# CCU_Sheet.net
KiCad netlist of a schematic drawn in Altium Designer
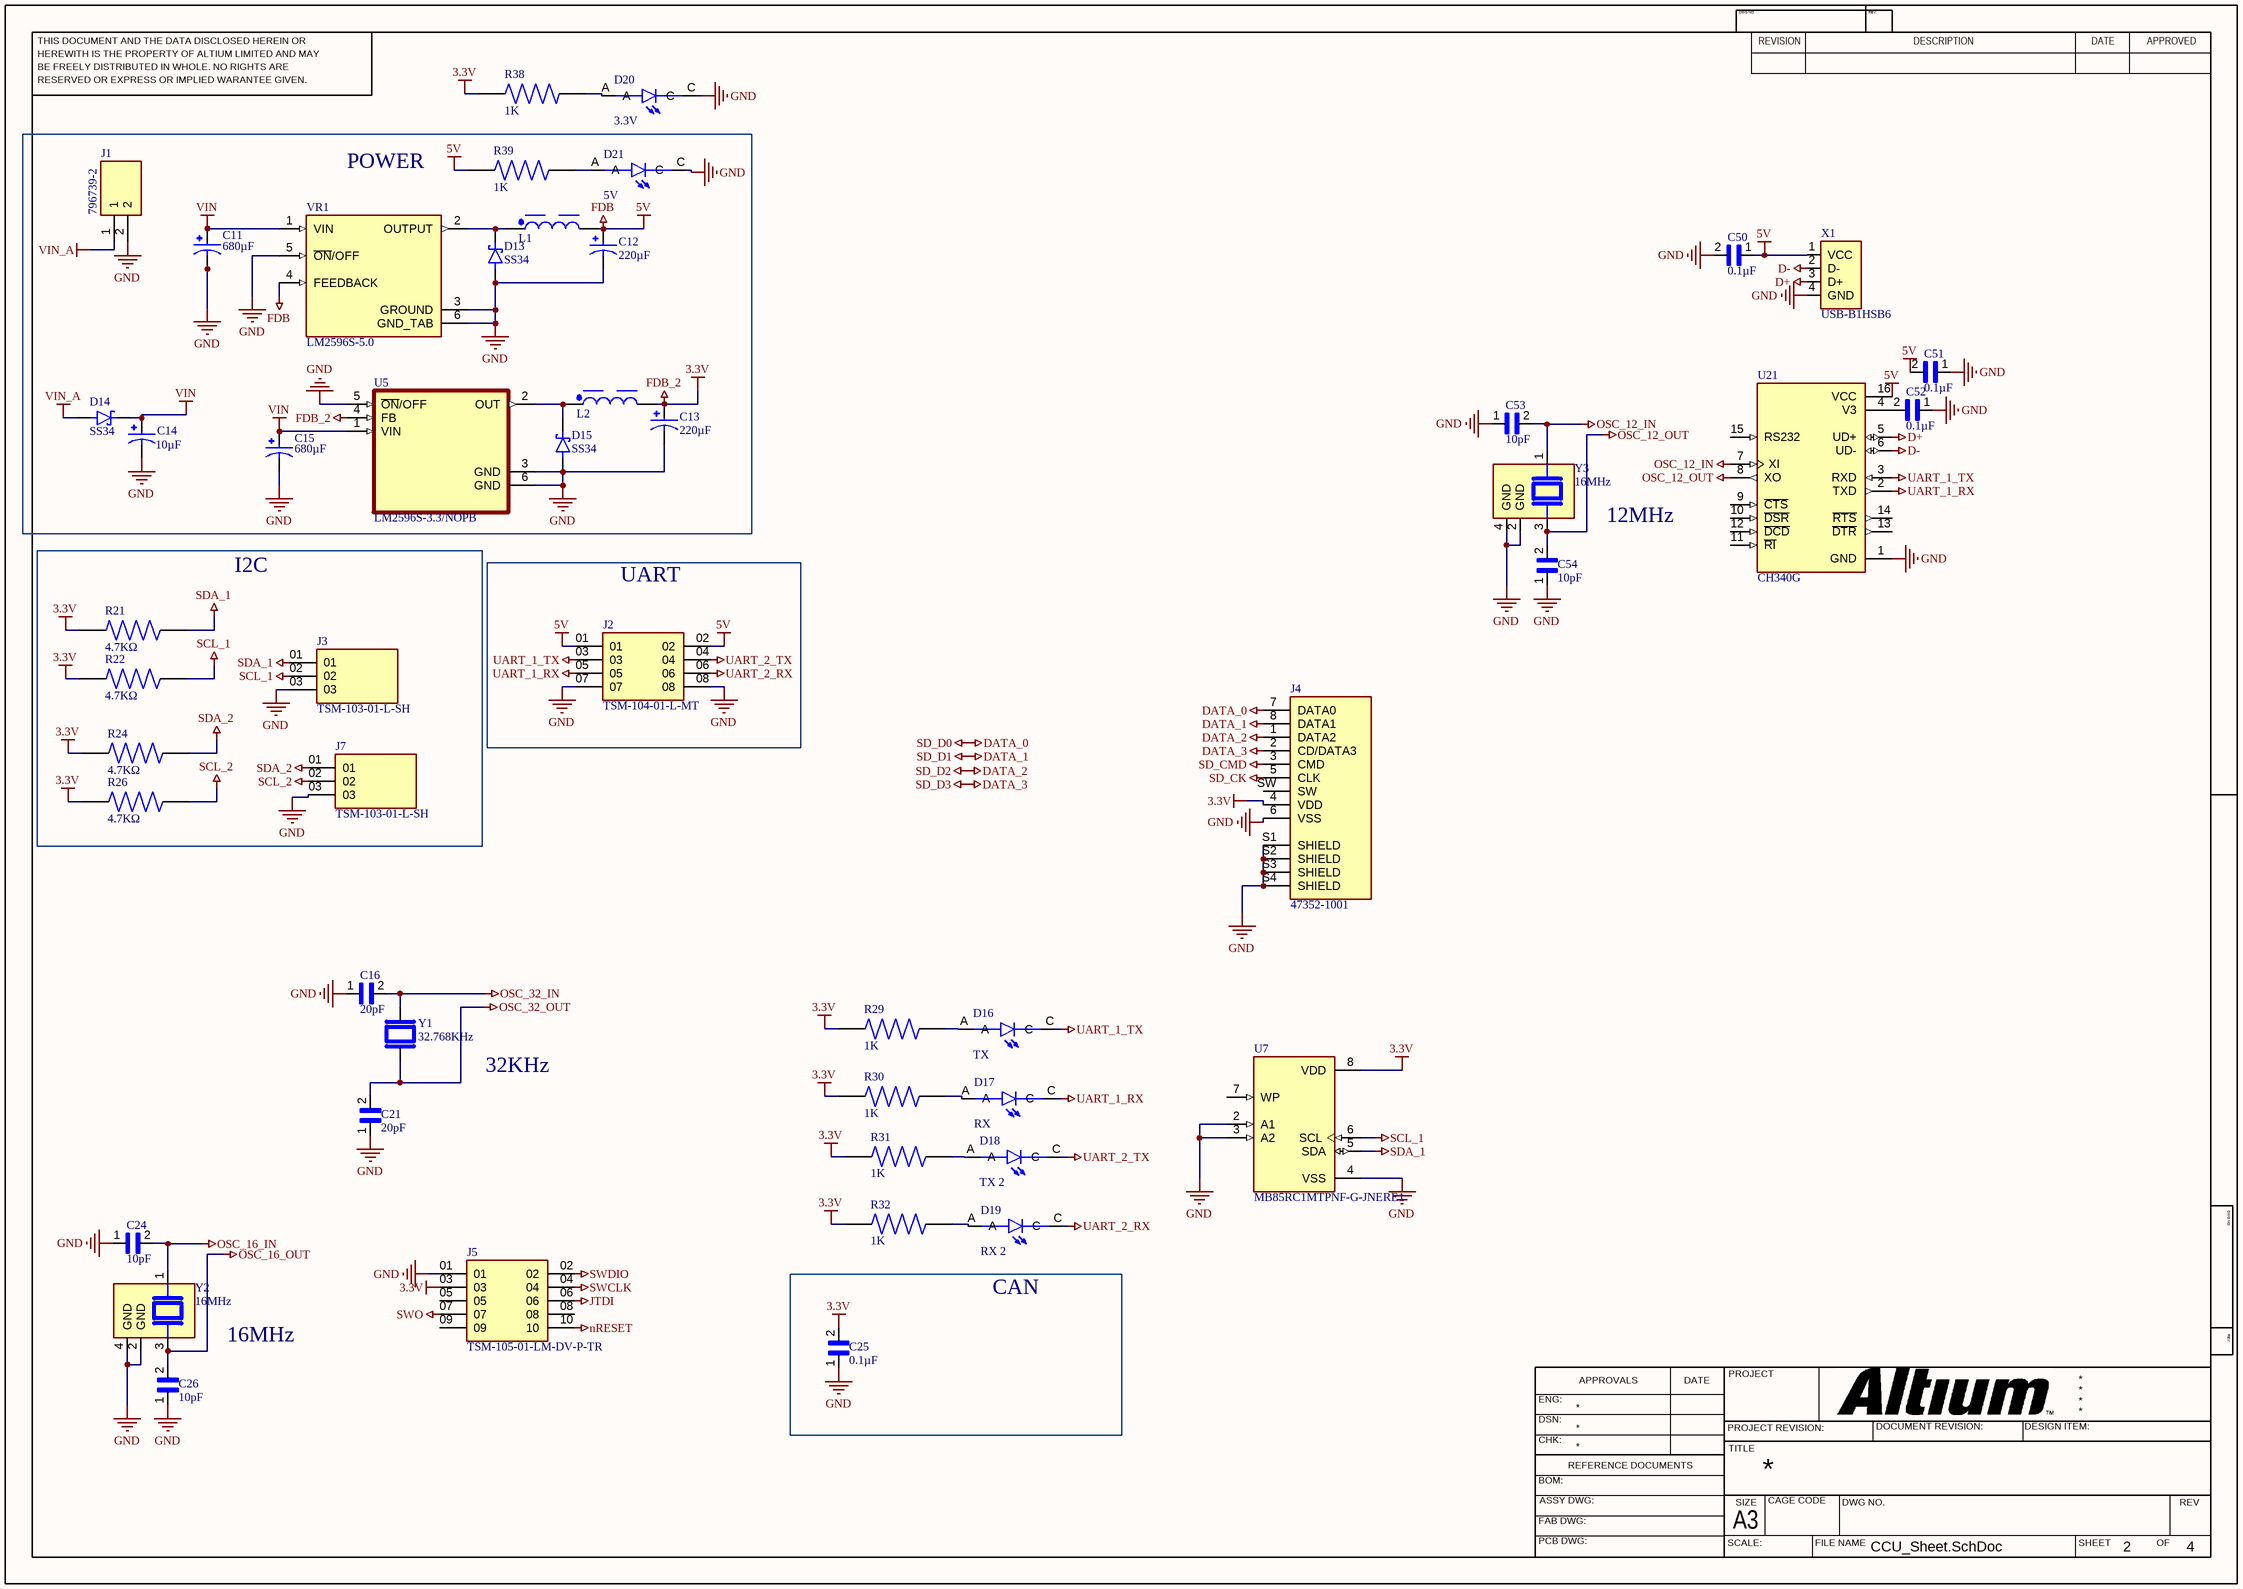
[diagram p0: CCU_Sheet.SchDoc]

(export (version "E")
  (design (tool "Eeschema 10.0.6"))
  (components
    (comp (ref "C11")
      (value "680µF")
      (footprint "CAP_EEEFN1E681UV")
      (description "CAP ALUM 680UF 20% 25V SMD")
      (fields (field (name "MF") "Panasonic Electronic Components") (field (name "MP") "EEE-FN1E681UV"))
      (libsource (lib "EEEFN1E681UV") (part "EEEFN1E681UV"))
    )
    (comp (ref "C12")
      (value "220µF")
      (footprint "CAP_EEEFP1V221AV")
      (description "CAP ALUM 220UF 20% 35V SMD")
      (fields (field (name "MF") "Panasonic Electronic Components") (field (name "MP") "EEE-FP1V221AV"))
      (libsource (lib "") (part "EEEFP1V221AV_1"))
    )
    (comp (ref "C13")
      (value "220µF")
      (footprint "CAP_EEEFP1V221AV")
      (description "CAP ALUM 220UF 20% 35V SMD")
      (fields (field (name "MF") "Panasonic Electronic Components") (field (name "MP") "EEE-FP1V221AV"))
      (libsource (lib "EEEFP1V221AV") (part "EEEFP1V221AV"))
    )
    (comp (ref "C14")
      (value "10µF")
      (footprint "CAPPRD500W50D500H1100")
      (description "10ÂµF 25V Aluminum Electrolytic Capacitors Radial, Can 2000 Hrs @ 85Â°C")
      (fields (field (name "MF") "Panasonic") (field (name "MP") "ECEA1EN100UB"))
      (libsource (lib "ECEA1EN100UB") (part "ECEA1EN100UB"))
    )
    (comp (ref "C15")
      (value "680µF")
      (footprint "CAP_EEEFN1E681UV")
      (description "CAP ALUM 680UF 20% 25V SMD")
      (fields (field (name "MF") "Panasonic Electronic Components") (field (name "MP") "EEE-FN1E681UV"))
      (libsource (lib "") (part "EEEFN1E681UV_1"))
    )
    (comp (ref "C16")
      (value "20pF")
      (footprint "CAPC1005X61N")
      (fields (field (name "MP") "VJ0402D200FXAAJ"))
      (libsource (lib "VJ0402D200FXAAJ") (part "VJ0402D200FXAAJ"))
    )
    (comp (ref "C21")
      (value "20pF")
      (footprint "CAPC1005X61N")
      (fields (field (name "MP") "VJ0402D200FXAAJ"))
      (libsource (lib "") (part "VJ0402D200FXAAJ_1"))
    )
    (comp (ref "C24")
      (value "10pF")
      (footprint "CAPC1005X61N")
      (fields (field (name "MP") "VJ0402D200FXAAJ"))
      (libsource (lib "VJ0402D200FXAAJ") (part "VJ0402D200FXAAJ"))
    )
    (comp (ref "C25")
      (value "0.1µF")
      (footprint "CAPC1608X90N")
      (description "Multilayer Ceramic Capacitors MLCC - SMD/SMT")
      (fields (field (name "MP") "06035C104MAZ2A"))
      (libsource (lib "") (part "06035C104MAZ2A_1"))
    )
    (comp (ref "C26")
      (value "10pF")
      (footprint "CAPC1005X61N")
      (fields (field (name "MP") "VJ0402D200FXAAJ"))
      (libsource (lib "") (part "VJ0402D200FXAAJ_1"))
    )
    (comp (ref "C50")
      (value "0.1µF")
      (footprint "CAPC1608X90N")
      (description "Multilayer Ceramic Capacitors MLCC - SMD/SMT")
      (fields (field (name "MP") "06035C104MAZ2A"))
      (libsource (lib "06035C104MAZ2A") (part "06035C104MAZ2A"))
    )
    (comp (ref "C51")
      (value "0.1µF")
      (footprint "CAPC1608X90N")
      (description "Multilayer Ceramic Capacitors MLCC - SMD/SMT")
      (fields (field (name "MP") "06035C104MAZ2A"))
      (libsource (lib "06035C104MAZ2A") (part "06035C104MAZ2A"))
    )
    (comp (ref "C52")
      (value "0.1µF")
      (footprint "CAPC1608X90N")
      (description "Multilayer Ceramic Capacitors MLCC - SMD/SMT")
      (fields (field (name "MP") "06035C104MAZ2A"))
      (libsource (lib "06035C104MAZ2A") (part "06035C104MAZ2A"))
    )
    (comp (ref "C53")
      (value "10pF")
      (footprint "CAPC1005X61N")
      (fields (field (name "MP") "VJ0402D200FXAAJ"))
      (libsource (lib "VJ0402D200FXAAJ") (part "VJ0402D200FXAAJ"))
    )
    (comp (ref "C54")
      (value "10pF")
      (footprint "CAPC1005X61N")
      (fields (field (name "MP") "VJ0402D200FXAAJ"))
      (libsource (lib "") (part "VJ0402D200FXAAJ_1"))
    )
    (comp (ref "D13")
      (value "SS34")
      (footprint "DIO_SS34")
      (description "3A, 40V, Schottky Rectifier")
      (fields (field (name "MF") "Taiwan Semiconductor"))
      (libsource (lib "SS34") (part "SS34"))
    )
    (comp (ref "D14")
      (value "SS34")
      (footprint "DIO_SS34")
      (description "3A, 40V, Schottky Rectifier")
      (fields (field (name "MF") "Taiwan Semiconductor"))
      (libsource (lib "SS34") (part "SS34"))
    )
    (comp (ref "D15")
      (value "SS34")
      (footprint "DIO_SS34")
      (description "3A, 40V, Schottky Rectifier")
      (fields (field (name "MF") "Taiwan Semiconductor"))
      (libsource (lib "SS34") (part "SS34"))
    )
    (comp (ref "D16")
      (value "TX")
      (footprint "LEDC2012X70N")
      (description "LED Uni-Color Green 4-Pin Chip 0805 T/R")
      (fields (field (name "MP") "597-3305-607F"))
      (libsource (lib "597-3305-607F") (part "597-3305-607F"))
    )
    (comp (ref "D17")
      (value "RX")
      (footprint "LEDC2012X70N")
      (description "LED Uni-Color Green 4-Pin Chip 0805 T/R")
      (fields (field (name "MP") "597-3305-607F"))
      (libsource (lib "597-3305-607F") (part "597-3305-607F"))
    )
    (comp (ref "D18")
      (value "TX 2")
      (footprint "LEDC2012X70N")
      (description "LED Uni-Color Green 4-Pin Chip 0805 T/R")
      (fields (field (name "MP") "597-3305-607F"))
      (libsource (lib "597-3305-607F") (part "597-3305-607F"))
    )
    (comp (ref "D19")
      (value "RX 2")
      (footprint "LEDC2012X70N")
      (description "LED Uni-Color Green 4-Pin Chip 0805 T/R")
      (fields (field (name "MP") "597-3305-607F"))
      (libsource (lib "597-3305-607F") (part "597-3305-607F"))
    )
    (comp (ref "D20")
      (value "3.3V")
      (footprint "LEDC2012X70N")
      (description "LED Uni-Color Green 4-Pin Chip 0805 T/R")
      (fields (field (name "MP") "597-3305-607F"))
      (libsource (lib "597-3305-607F") (part "597-3305-607F"))
    )
    (comp (ref "D21")
      (value "5V")
      (footprint "LEDC2012X70N")
      (description "LED Uni-Color Green 4-Pin Chip 0805 T/R")
      (fields (field (name "MP") "597-3305-607F"))
      (libsource (lib "597-3305-607F") (part "597-3305-607F"))
    )
    (comp (ref "J1")
      (value "796739-2")
      (footprint "TE_796739-2")
      (description "Conn Terminal Block F 2 POS 9.53mm Solder RA Thru-Hole 32A/Contact")
      (fields (field (name "MF") "TE Connectivity"))
      (libsource (lib "796739-2") (part "796739-2"))
    )
    (comp (ref "J2")
      (value "TSM-104-01-L-MT")
      (footprint "SAMTEC_TSM-104-01-L-MT")
      (description "TSM Series .100 Surface Mount Terminal Strip")
      (fields (field (name "MF") "Samtec"))
      (libsource (lib "TSM-104-01-L-MT") (part "TSM-104-01-L-MT"))
    )
    (comp (ref "J3")
      (value "TSM-103-01-L-SH")
      (footprint "SAMTEC_TSM-103-01-L-SH")
      (fields (field (name "MF") "Samtec Inc."))
      (libsource (lib "TSM-103-01-L-SH (1)") (part "TSM-103-01-L-SH"))
    )
    (comp (ref "J4")
      (value "47352-1001")
      (footprint "MOLEX_47352-1001")
      (description "8 (6 + 2) Position Card Connector Secure Digital - microSDâ„¢ Surface Mount, Right Angle Gold")
      (fields (field (name "MP") "473521001") (field (name "MF") "Molex"))
      (libsource (lib "47352-1001") (part "47352-1001"))
    )
    (comp (ref "J5")
      (value "TSM-105-01-LM-DV-P-TR")
      (footprint "SAMTEC_TSM-105-01-LM-DV-P-TR")
      (description "TSM - Samtec 2.54mm Dual Row Vertical Surface Mount Header 5.84mm Post Height (01) - Fast Stock")
      (fields (field (name "MF") "Samtec"))
      (libsource (lib "TSM-105-01-LM-DV-P-TR") (part "TSM-105-01-LM-DV-P-TR"))
    )
    (comp (ref "J7")
      (value "TSM-103-01-L-SH")
      (footprint "SAMTEC_TSM-103-01-L-SH")
      (fields (field (name "MF") "Samtec Inc."))
      (libsource (lib "TSM-103-01-L-SH (1)") (part "TSM-103-01-L-SH"))
    )
    (comp (ref "L1")
      (value "33uH, 4.2A")
      (footprint "WE-PD_1210")
      (description "WE-PD SMT Power Inductor, size 1210, 33uH, 4.2A, 45mOhm")
      (fields
        (field (name "MANUFACTURER PART NUMBER") "7447709330")
        (field (name "MANUFACTURER") "Wurth Elektronik")
      )
      (libsource (lib "Altium_WE-PD_rev22g") (part "7447709330"))
    )
    (comp (ref "L2")
      (value "33uH, 4.2A")
      (footprint "WE-PD_1210")
      (description "WE-PD SMT Power Inductor, size 1210, 33uH, 4.2A, 45mOhm")
      (fields
        (field (name "MANUFACTURER PART NUMBER") "7447709330")
        (field (name "MANUFACTURER") "Wurth Elektronik")
      )
      (libsource (lib "Altium_WE-PD_rev22g") (part "7447709330"))
    )
    (comp (ref "R21")
      (value "4.7KΩ")
      (footprint "RES_ERJS06J472V")
      (fields (field (name "MP") "ERJS06J472V"))
      (libsource (lib "ERJS06J472V") (part "ERJS06J472V"))
    )
    (comp (ref "R22")
      (value "4.7KΩ")
      (footprint "RES_ERJS06J472V")
      (fields (field (name "MP") "ERJS06J472V"))
      (libsource (lib "ERJS06J472V") (part "ERJS06J472V"))
    )
    (comp (ref "R24")
      (value "4.7KΩ")
      (footprint "RES_ERJS06J472V")
      (fields (field (name "MP") "ERJS06J472V"))
      (libsource (lib "ERJS06J472V") (part "ERJS06J472V"))
    )
    (comp (ref "R26")
      (value "4.7KΩ")
      (footprint "RES_ERJS06J472V")
      (fields (field (name "MP") "ERJS06J472V"))
      (libsource (lib "ERJS06J472V") (part "ERJS06J472V"))
    )
    (comp (ref "R29")
      (value "1K")
      (footprint "RESC3116X65N")
      (fields (field (name "MF") "Yageo Corporation") (field (name "MP") "RC1206JR071KL"))
      (libsource (lib "RC1206JR-071KL") (part "RC1206JR-071KL"))
    )
    (comp (ref "R30")
      (value "1K")
      (footprint "RESC3116X65N")
      (fields (field (name "MF") "Yageo Corporation") (field (name "MP") "RC1206JR071KL"))
      (libsource (lib "RC1206JR-071KL") (part "RC1206JR-071KL"))
    )
    (comp (ref "R31")
      (value "1K")
      (footprint "RESC3116X65N")
      (fields (field (name "MF") "Yageo Corporation") (field (name "MP") "RC1206JR071KL"))
      (libsource (lib "RC1206JR-071KL") (part "RC1206JR-071KL"))
    )
    (comp (ref "R32")
      (value "1K")
      (footprint "RESC3116X65N")
      (fields (field (name "MF") "Yageo Corporation") (field (name "MP") "RC1206JR071KL"))
      (libsource (lib "RC1206JR-071KL") (part "RC1206JR-071KL"))
    )
    (comp (ref "R38")
      (value "1K")
      (footprint "RESC3116X65N")
      (fields (field (name "MF") "Yageo Corporation") (field (name "MP") "RC1206JR071KL"))
      (libsource (lib "RC1206JR-071KL") (part "RC1206JR-071KL"))
    )
    (comp (ref "R39")
      (value "1K")
      (footprint "RESC3116X65N")
      (fields (field (name "MF") "Yageo Corporation") (field (name "MP") "RC1206JR071KL"))
      (libsource (lib "RC1206JR-071KL") (part "RC1206JR-071KL"))
    )
    (comp (ref "U5")
      (value "LM2596S-3.3/NOPB")
      (footprint "VREG_LM2596S-3.3/NOPB")
      (libsource (lib "LM2596S-3.3_NOPB") (part "LM2596S-3.3/NOPB"))
    )
    (comp (ref "U7")
      (value "MB85RC1MTPNF-G-JNERE1")
      (footprint "SOIC127P600X175-8N")
      (description "FRAM _Ferroelectric RAM_ Memory IC 1Mb _128K x 8_ IÂ²C 3.4MHz 130ns 8-SOP")
      (fields (field (name "MF") "Fujitsu Electronics"))
      (libsource (lib "MB85RC1MTPNF-G-JNERE1") (part "MB85RC1MTPNF-G-JNERE1"))
    )
    (comp (ref "U21")
      (value "CH340G")
      (footprint "SOIC127P600X180-16N")
      (description "USB Interface Integrated Circuit")
      (fields (field (name "MP") "Ch340G") (field (name "MF") "WCH"))
      (libsource (lib "CH340G") (part "CH340G"))
    )
    (comp (ref "VR1")
      (value "LM2596S-5.0")
      (footprint "TO170P1524X483-6N")
      (description "SIMPLE SWITCHER&reg; 4.5V to 40V, 3A Low Component Count Step-Down Regulator")
      (fields (field (name "MP") "LM2596S-5.0/NOPB") (field (name "MF") "Texas Instruments"))
      (libsource (lib "LM2596S-5.0") (part "LM2596S-5.0"))
    )
    (comp (ref "X1")
      (value "USB-B1HSB6")
      (footprint "OST_USB-B1HSB6")
      (description "USB-B (USB TYPE-B) - Receptacle Connector 4 Position Through Hole, Right Angle")
      (fields (field (name "MF") "On Shore"))
      (libsource (lib "USB-B1HSB6") (part "USB-B1HSB6"))
    )
    (comp (ref "Y1")
      (value "32.768KHz")
      (footprint "XTAL_ABS06-32.768KHZ-9-1-T")
      (description "32.768 kHz Â±10ppm Crystal 9pF 90 kOhms 2-SMD, No Lead")
      (fields (field (name "MF") "Abracon") (field (name "MP") "ABS06-32.768KHZ-9-1-T"))
      (libsource (lib "ABS06-32.768KHZ-9-1-T") (part "ABS06-32.768KHZ-9-1-T"))
    )
    (comp (ref "Y2")
      (value "16MHz")
      (footprint "XTAL_7M25090002")
      (description "25 MHz Â±10ppm Crystal 18pF 4-SMD, No Lead")
      (fields (field (name "MF") "TXC") (field (name "MP") "7M25090002"))
      (libsource (lib "7M25090002") (part "7M25090002"))
    )
    (comp (ref "Y3")
      (value "16MHz")
      (footprint "XTAL_7M25090002")
      (description "25 MHz Â±10ppm Crystal 18pF 4-SMD, No Lead")
      (fields (field (name "MF") "TXC") (field (name "MP") "7M25090002"))
      (libsource (lib "7M25090002") (part "7M25090002"))
    )
  )
  (nets
    (net (code "1") (name "3.3V") (class "Default")
      (node (ref "C13") (pin "1") (pinfunction "1_1") (pintype "passive"))
      (node (ref "C25") (pin "2") (pinfunction "2_2") (pintype "passive"))
      (node (ref "J4") (pin "4") (pinfunction "VDD_4") (pintype "passive"))
      (node (ref "J5") (pin "03") (pinfunction "03_03") (pintype "passive"))
      (node (ref "L2") (pin "2") (pinfunction "2_2") (pintype "passive"))
      (node (ref "R21") (pin "2") (pinfunction "2_2") (pintype "passive"))
      (node (ref "R22") (pin "1") (pinfunction "1_1") (pintype "passive"))
      (node (ref "R24") (pin "2") (pinfunction "2_2") (pintype "passive"))
      (node (ref "R26") (pin "1") (pinfunction "1_1") (pintype "passive"))
      (node (ref "R29") (pin "1") (pinfunction "1_1") (pintype "passive"))
      (node (ref "R30") (pin "1") (pinfunction "1_1") (pintype "passive"))
      (node (ref "R31") (pin "1") (pinfunction "1_1") (pintype "passive"))
      (node (ref "R32") (pin "1") (pinfunction "1_1") (pintype "passive"))
      (node (ref "R38") (pin "1") (pinfunction "1_1") (pintype "passive"))
      (node (ref "U5") (pin "4") (pinfunction "FB_4") (pintype "input"))
      (node (ref "U7") (pin "8") (pinfunction "VDD_8") (pintype "power_in"))
    )
    (net (code "2") (name "5V") (class "Default")
      (node (ref "C12") (pin "1") (pinfunction "1_1") (pintype "passive"))
      (node (ref "C50") (pin "1") (pinfunction "1_1") (pintype "passive"))
      (node (ref "C51") (pin "2") (pinfunction "2_2") (pintype "passive"))
      (node (ref "J2") (pin "01") (pinfunction "01_01") (pintype "passive"))
      (node (ref "J2") (pin "02") (pinfunction "02_02") (pintype "passive"))
      (node (ref "L1") (pin "2") (pinfunction "2_2") (pintype "passive"))
      (node (ref "R39") (pin "1") (pinfunction "1_1") (pintype "passive"))
      (node (ref "U21") (pin "16") (pinfunction "VCC_16") (pintype "power_in"))
      (node (ref "VR1") (pin "4") (pinfunction "FEEDBACK_4") (pintype "input"))
      (node (ref "X1") (pin "1") (pinfunction "VCC_1") (pintype "power_in"))
    )
    (net (code "3") (name "D+") (class "Default")
      (node (ref "U21") (pin "5") (pinfunction "UD+_5") (pintype "bidirectional"))
      (node (ref "X1") (pin "3") (pinfunction "D+_3") (pintype "bidirectional"))
    )
    (net (code "4") (name "D-") (class "Default")
      (node (ref "U21") (pin "6") (pinfunction "UD-_6") (pintype "bidirectional"))
      (node (ref "X1") (pin "2") (pinfunction "D-_2") (pintype "bidirectional"))
    )
    (net (code "5") (name "DATA_0") (class "Default")
      (node (ref "J4") (pin "7") (pinfunction "DATA0_7") (pintype "passive"))
    )
    (net (code "6") (name "DATA_1") (class "Default")
      (node (ref "J4") (pin "8") (pinfunction "DATA1_8") (pintype "passive"))
    )
    (net (code "7") (name "DATA_2") (class "Default")
      (node (ref "J4") (pin "1") (pinfunction "DATA2_1") (pintype "passive"))
    )
    (net (code "8") (name "DATA_3") (class "Default")
      (node (ref "J4") (pin "2") (pinfunction "CD/DATA3_2") (pintype "passive"))
    )
    (net (code "9") (name "GND") (class "Default")
      (node (ref "C11") (pin "2") (pinfunction "2_2") (pintype "passive"))
      (node (ref "C12") (pin "2") (pinfunction "2_2") (pintype "passive"))
      (node (ref "C13") (pin "2") (pinfunction "2_2") (pintype "passive"))
      (node (ref "C14") (pin "N") (pinfunction "N_N") (pintype "passive"))
      (node (ref "C15") (pin "2") (pinfunction "2_2") (pintype "passive"))
      (node (ref "C16") (pin "1") (pinfunction "1_1") (pintype "passive"))
      (node (ref "C21") (pin "1") (pinfunction "1_1") (pintype "passive"))
      (node (ref "C24") (pin "1") (pinfunction "1_1") (pintype "passive"))
      (node (ref "C25") (pin "1") (pinfunction "1_1") (pintype "passive"))
      (node (ref "C26") (pin "1") (pinfunction "1_1") (pintype "passive"))
      (node (ref "C50") (pin "2") (pinfunction "2_2") (pintype "passive"))
      (node (ref "C51") (pin "1") (pinfunction "1_1") (pintype "passive"))
      (node (ref "C52") (pin "1") (pinfunction "1_1") (pintype "passive"))
      (node (ref "C53") (pin "1") (pinfunction "1_1") (pintype "passive"))
      (node (ref "C54") (pin "1") (pinfunction "1_1") (pintype "passive"))
      (node (ref "D13") (pin "A") (pinfunction "A_A") (pintype "passive"))
      (node (ref "D15") (pin "A") (pinfunction "A_A") (pintype "passive"))
      (node (ref "D20") (pin "C") (pinfunction "C_C") (pintype "passive"))
      (node (ref "D21") (pin "C") (pinfunction "C_C") (pintype "passive"))
      (node (ref "J1") (pin "2") (pinfunction "2_2") (pintype "passive"))
      (node (ref "J2") (pin "07") (pinfunction "07_07") (pintype "passive"))
      (node (ref "J2") (pin "08") (pinfunction "08_08") (pintype "passive"))
      (node (ref "J3") (pin "03") (pinfunction "03_03") (pintype "passive"))
      (node (ref "J4") (pin "6") (pinfunction "VSS_6") (pintype "passive"))
      (node (ref "J4") (pin "S1") (pinfunction "SHIELD_S1") (pintype "passive"))
      (node (ref "J4") (pin "S2") (pinfunction "SHIELD_S2") (pintype "passive"))
      (node (ref "J4") (pin "S3") (pinfunction "SHIELD_S3") (pintype "passive"))
      (node (ref "J4") (pin "S4") (pinfunction "SHIELD_S4") (pintype "passive"))
      (node (ref "J5") (pin "01") (pinfunction "01_01") (pintype "passive"))
      (node (ref "J7") (pin "03") (pinfunction "03_03") (pintype "passive"))
      (node (ref "U21") (pin "1") (pinfunction "GND_1") (pintype "power_in"))
      (node (ref "U5") (pin "3") (pinfunction "GND_3") (pintype "power_in"))
      (node (ref "U5") (pin "5") (pinfunction "~{ON}/OFF_5") (pintype "input"))
      (node (ref "U5") (pin "6") (pinfunction "GND_6") (pintype "power_in"))
      (node (ref "U7") (pin "2") (pinfunction "A1_2") (pintype "input"))
      (node (ref "U7") (pin "3") (pinfunction "A2_3") (pintype "input"))
      (node (ref "U7") (pin "4") (pinfunction "VSS_4") (pintype "power_in"))
      (node (ref "VR1") (pin "3") (pinfunction "GROUND_3") (pintype "power_in"))
      (node (ref "VR1") (pin "5") (pinfunction "~{ON}/OFF_5") (pintype "input"))
      (node (ref "VR1") (pin "6") (pinfunction "GND_TAB_6") (pintype "power_in"))
      (node (ref "X1") (pin "4") (pinfunction "GND_4") (pintype "power_in"))
      (node (ref "Y2") (pin "2") (pinfunction "GND_2") (pintype "power_in"))
      (node (ref "Y2") (pin "4") (pinfunction "GND_4") (pintype "power_in"))
      (node (ref "Y3") (pin "2") (pinfunction "GND_2") (pintype "power_in"))
      (node (ref "Y3") (pin "4") (pinfunction "GND_4") (pintype "power_in"))
    )
    (net (code "10") (name "JTDI") (class "Default")
      (node (ref "J5") (pin "06") (pinfunction "06_06") (pintype "passive"))
    )
    (net (code "11") (name "Net-(D13-K)") (class "Default")
      (node (ref "D13") (pin "C") (pinfunction "K_C") (pintype "passive"))
      (node (ref "L1") (pin "1") (pinfunction "1_1") (pintype "passive"))
      (node (ref "VR1") (pin "2") (pinfunction "OUTPUT_2") (pintype "output"))
    )
    (net (code "12") (name "Net-(D15-K)") (class "Default")
      (node (ref "D15") (pin "C") (pinfunction "K_C") (pintype "passive"))
      (node (ref "L2") (pin "1") (pinfunction "1_1") (pintype "passive"))
      (node (ref "U5") (pin "2") (pinfunction "OUT_2") (pintype "output"))
    )
    (net (code "13") (name "Net-(D16-PadA)") (class "Default")
      (node (ref "D16") (pin "A") (pinfunction "A_A") (pintype "passive"))
      (node (ref "R29") (pin "2") (pinfunction "2_2") (pintype "passive"))
    )
    (net (code "14") (name "Net-(D17-PadA)") (class "Default")
      (node (ref "D17") (pin "A") (pinfunction "A_A") (pintype "passive"))
      (node (ref "R30") (pin "2") (pinfunction "2_2") (pintype "passive"))
    )
    (net (code "15") (name "Net-(D18-PadA)") (class "Default")
      (node (ref "D18") (pin "A") (pinfunction "A_A") (pintype "passive"))
      (node (ref "R31") (pin "2") (pinfunction "2_2") (pintype "passive"))
    )
    (net (code "16") (name "Net-(D19-PadA)") (class "Default")
      (node (ref "D19") (pin "A") (pinfunction "A_A") (pintype "passive"))
      (node (ref "R32") (pin "2") (pinfunction "2_2") (pintype "passive"))
    )
    (net (code "17") (name "Net-(D20-PadA)") (class "Default")
      (node (ref "D20") (pin "A") (pinfunction "A_A") (pintype "passive"))
      (node (ref "R38") (pin "2") (pinfunction "2_2") (pintype "passive"))
    )
    (net (code "18") (name "Net-(D21-PadA)") (class "Default")
      (node (ref "D21") (pin "A") (pinfunction "A_A") (pintype "passive"))
      (node (ref "R39") (pin "2") (pinfunction "2_2") (pintype "passive"))
    )
    (net (code "19") (name "Net-(U21-V3)") (class "Default")
      (node (ref "C52") (pin "2") (pinfunction "2_2") (pintype "passive"))
      (node (ref "U21") (pin "4") (pinfunction "V3_4") (pintype "power_in"))
    )
    (net (code "20") (name "OSC_12_IN") (class "Default")
      (node (ref "C53") (pin "2") (pinfunction "2_2") (pintype "passive"))
      (node (ref "U21") (pin "7") (pinfunction "XI_7") (pintype "input"))
      (node (ref "Y3") (pin "1") (pinfunction "1_1") (pintype "passive"))
    )
    (net (code "21") (name "OSC_12_OUT") (class "Default")
      (node (ref "C54") (pin "2") (pinfunction "2_2") (pintype "passive"))
      (node (ref "U21") (pin "8") (pinfunction "XO_8") (pintype "output"))
      (node (ref "Y3") (pin "3") (pinfunction "2_3") (pintype "passive"))
    )
    (net (code "22") (name "OSC_16_IN") (class "Default")
      (node (ref "C24") (pin "2") (pinfunction "2_2") (pintype "passive"))
      (node (ref "Y2") (pin "1") (pinfunction "1_1") (pintype "passive"))
    )
    (net (code "23") (name "OSC_16_OUT") (class "Default")
      (node (ref "C26") (pin "2") (pinfunction "2_2") (pintype "passive"))
      (node (ref "Y2") (pin "3") (pinfunction "2_3") (pintype "passive"))
    )
    (net (code "24") (name "OSC_32_IN") (class "Default")
      (node (ref "C16") (pin "2") (pinfunction "2_2") (pintype "passive"))
      (node (ref "Y1") (pin "2") (pinfunction "2_2") (pintype "passive"))
    )
    (net (code "25") (name "OSC_32_OUT") (class "Default")
      (node (ref "C21") (pin "2") (pinfunction "2_2") (pintype "passive"))
      (node (ref "Y1") (pin "1") (pinfunction "1_1") (pintype "passive"))
    )
    (net (code "26") (name "SCL_1") (class "Default")
      (node (ref "J3") (pin "02") (pinfunction "02_02") (pintype "passive"))
      (node (ref "R22") (pin "2") (pinfunction "2_2") (pintype "passive"))
      (node (ref "U7") (pin "6") (pinfunction "SCL_6") (pintype "input"))
    )
    (net (code "27") (name "SCL_2") (class "Default")
      (node (ref "J7") (pin "02") (pinfunction "02_02") (pintype "passive"))
      (node (ref "R26") (pin "2") (pinfunction "2_2") (pintype "passive"))
    )
    (net (code "28") (name "SDA_1") (class "Default")
      (node (ref "J3") (pin "01") (pinfunction "01_01") (pintype "passive"))
      (node (ref "R21") (pin "1") (pinfunction "1_1") (pintype "passive"))
      (node (ref "U7") (pin "5") (pinfunction "SDA_5") (pintype "bidirectional"))
    )
    (net (code "29") (name "SDA_2") (class "Default")
      (node (ref "J7") (pin "01") (pinfunction "01_01") (pintype "passive"))
      (node (ref "R24") (pin "1") (pinfunction "1_1") (pintype "passive"))
    )
    (net (code "30") (name "SD_CK") (class "Default")
      (node (ref "J4") (pin "5") (pinfunction "CLK_5") (pintype "passive"))
    )
    (net (code "31") (name "SD_CMD") (class "Default")
      (node (ref "J4") (pin "3") (pinfunction "CMD_3") (pintype "passive"))
    )
    (net (code "32") (name "SWCLK") (class "Default")
      (node (ref "J5") (pin "04") (pinfunction "04_04") (pintype "passive"))
    )
    (net (code "33") (name "SWDIO") (class "Default")
      (node (ref "J5") (pin "02") (pinfunction "02_02") (pintype "passive"))
    )
    (net (code "34") (name "SWO") (class "Default")
      (node (ref "J5") (pin "07") (pinfunction "07_07") (pintype "passive"))
    )
    (net (code "35") (name "UART_1_RX") (class "Default")
      (node (ref "D17") (pin "C") (pinfunction "C_C") (pintype "passive"))
      (node (ref "J2") (pin "05") (pinfunction "05_05") (pintype "passive"))
      (node (ref "U21") (pin "2") (pinfunction "TXD_2") (pintype "output"))
    )
    (net (code "36") (name "UART_1_TX") (class "Default")
      (node (ref "D16") (pin "C") (pinfunction "C_C") (pintype "passive"))
      (node (ref "J2") (pin "03") (pinfunction "03_03") (pintype "passive"))
      (node (ref "U21") (pin "3") (pinfunction "RXD_3") (pintype "input"))
    )
    (net (code "37") (name "UART_2_RX") (class "Default")
      (node (ref "D19") (pin "C") (pinfunction "C_C") (pintype "passive"))
      (node (ref "J2") (pin "06") (pinfunction "06_06") (pintype "passive"))
    )
    (net (code "38") (name "UART_2_TX") (class "Default")
      (node (ref "D18") (pin "C") (pinfunction "C_C") (pintype "passive"))
      (node (ref "J2") (pin "04") (pinfunction "04_04") (pintype "passive"))
    )
    (net (code "39") (name "VIN") (class "Default")
      (node (ref "C11") (pin "1") (pinfunction "1_1") (pintype "passive"))
      (node (ref "C14") (pin "P") (pinfunction "P_P") (pintype "passive"))
      (node (ref "C15") (pin "1") (pinfunction "1_1") (pintype "passive"))
      (node (ref "D14") (pin "C") (pinfunction "K_C") (pintype "passive"))
      (node (ref "U5") (pin "1") (pinfunction "VIN_1") (pintype "input"))
      (node (ref "VR1") (pin "1") (pinfunction "VIN_1") (pintype "input"))
    )
    (net (code "40") (name "VIN_A") (class "Default")
      (node (ref "D14") (pin "A") (pinfunction "A_A") (pintype "passive"))
      (node (ref "J1") (pin "1") (pinfunction "1_1") (pintype "passive"))
    )
    (net (code "41") (name "nRESET") (class "Default")
      (node (ref "J5") (pin "10") (pinfunction "10_10") (pintype "passive"))
    )
    (net (code "42") (name "unconnected-(J4-PadSW)") (class "Default")
      (node (ref "J4") (pin "SW") (pinfunction "SW_SW") (pintype "passive"))
    )
    (net (code "43") (name "unconnected-(J5-Pad05)") (class "Default")
      (node (ref "J5") (pin "05") (pinfunction "05_05") (pintype "passive"))
    )
    (net (code "44") (name "unconnected-(J5-Pad08)") (class "Default")
      (node (ref "J5") (pin "08") (pinfunction "08_08") (pintype "passive"))
    )
    (net (code "45") (name "unconnected-(J5-Pad09)") (class "Default")
      (node (ref "J5") (pin "09") (pinfunction "09_09") (pintype "passive"))
    )
    (net (code "46") (name "unconnected-(U7-WP-Pad7)") (class "Default")
      (node (ref "U7") (pin "7") (pinfunction "WP_7") (pintype "input"))
    )
    (net (code "47") (name "unconnected-(U21-RS232-Pad15)") (class "Default")
      (node (ref "U21") (pin "15") (pinfunction "RS232_15") (pintype "input"))
    )
    (net (code "48") (name "unconnected-(U21-~{CTS}-Pad9)") (class "Default")
      (node (ref "U21") (pin "9") (pinfunction "~{CTS}_9") (pintype "input"))
    )
    (net (code "49") (name "unconnected-(U21-~{DCD}-Pad12)") (class "Default")
      (node (ref "U21") (pin "12") (pinfunction "~{DCD}_12") (pintype "input"))
    )
    (net (code "50") (name "unconnected-(U21-~{DSR}-Pad10)") (class "Default")
      (node (ref "U21") (pin "10") (pinfunction "~{DSR}_10") (pintype "input"))
    )
    (net (code "51") (name "unconnected-(U21-~{DTR}-Pad13)") (class "Default")
      (node (ref "U21") (pin "13") (pinfunction "~{DTR}_13") (pintype "output"))
    )
    (net (code "52") (name "unconnected-(U21-~{RI}-Pad11)") (class "Default")
      (node (ref "U21") (pin "11") (pinfunction "~{RI}_11") (pintype "input"))
    )
    (net (code "53") (name "unconnected-(U21-~{RTS}-Pad14)") (class "Default")
      (node (ref "U21") (pin "14") (pinfunction "~{RTS}_14") (pintype "output"))
    )
  )
)
